# PRSC-2101-THCFM-1V3_eagle7.net
KiCad netlist of a schematic drawn in EAGLE
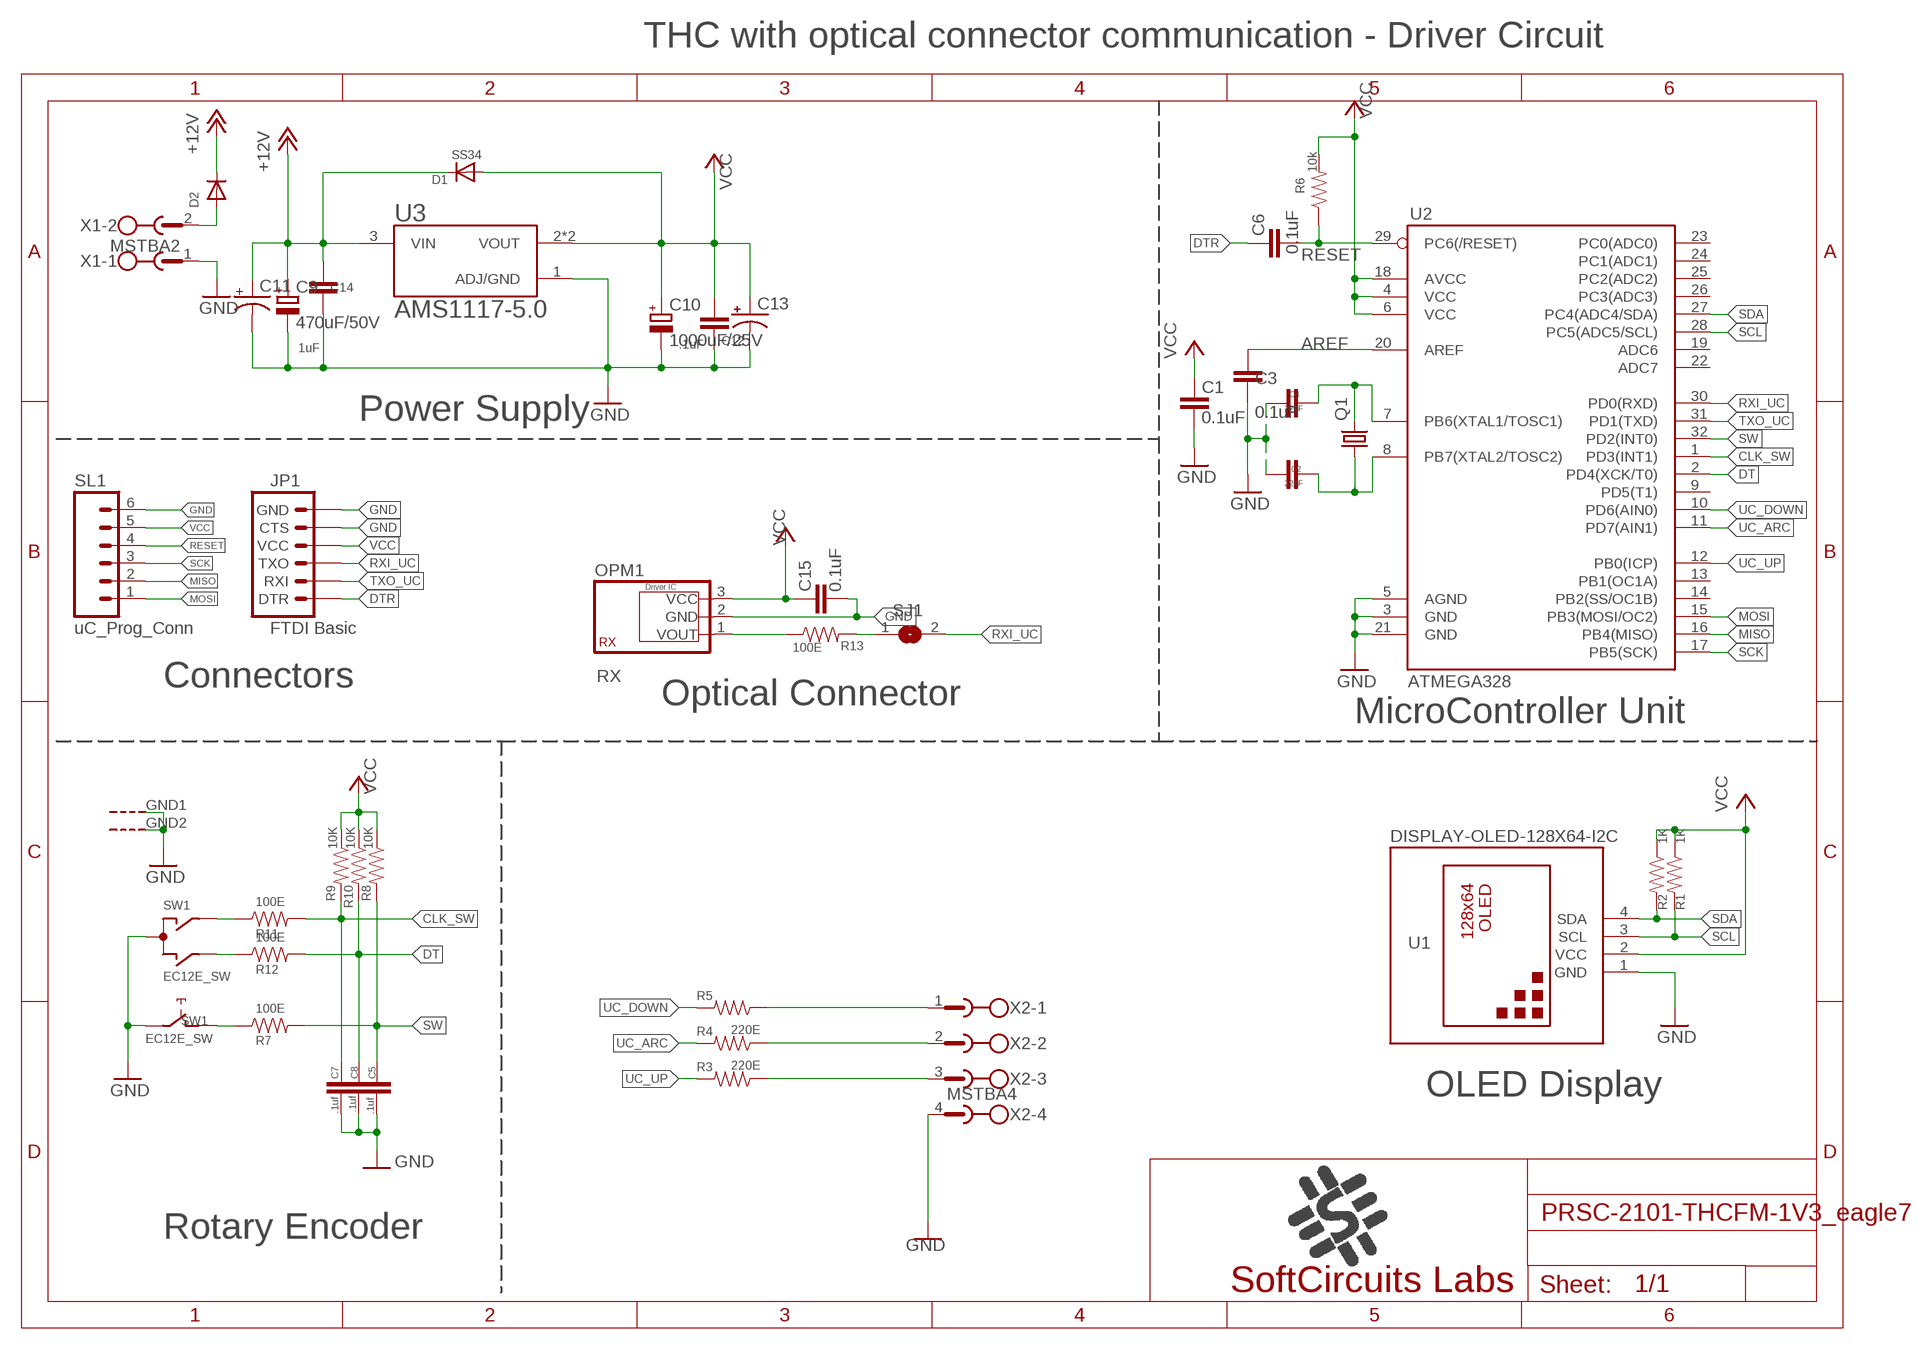
[diagram p0: schematic, sheet 1]

(export (version "E")
  (design (tool "Eeschema 10.0.6"))
  (components
    (comp (ref "C1")
      (value "0.1uF")
      (footprint "eagle-import:C1206")
      (libsource (lib "eagle-import") (part "C-EUC1206"))
    )
    (comp (ref "C2")
      (value "22pF")
      (footprint "eagle-import:C1206")
      (libsource (lib "eagle-import") (part "C-EUC1206"))
    )
    (comp (ref "C3")
      (value "0.1uF")
      (footprint "eagle-import:C1206")
      (libsource (lib "eagle-import") (part "C-EUC1206"))
    )
    (comp (ref "C4")
      (value "22pF")
      (footprint "eagle-import:C1206")
      (libsource (lib "eagle-import") (part "C-EUC1206"))
    )
    (comp (ref "C5")
      (value ".1uf")
      (footprint "eagle-import:C1206")
      (libsource (lib "eagle-import") (part "C-EUC1206"))
    )
    (comp (ref "C6")
      (value "0.1uF")
      (footprint "eagle-import:C1206")
      (libsource (lib "eagle-import") (part "C-EUC1206"))
    )
    (comp (ref "C7")
      (value ".1uf")
      (footprint "eagle-import:C1206")
      (libsource (lib "eagle-import") (part "C-EUC1206"))
    )
    (comp (ref "C8")
      (value ".1uf")
      (footprint "eagle-import:C1206")
      (libsource (lib "eagle-import") (part "C-EUC1206"))
    )
    (comp (ref "C9")
      (value "470uF/50V")
      (footprint "eagle-import:153CLV-1010")
      (libsource (lib "eagle-import") (part "CPOL-EU153CLV-1010"))
    )
    (comp (ref "C10")
      (value "1000uF/25V")
      (footprint "eagle-import:153CLV-1010")
      (libsource (lib "eagle-import") (part "CPOL-EU153CLV-1010"))
    )
    (comp (ref "C11")
      (value "CAP_POL3528-KIT")
      (footprint "eagle-import:EIA3528-KIT")
      (libsource (lib "eagle-import") (part "CAP_POL3528-KIT"))
    )
    (comp (ref "C12")
      (value ".1uF")
      (footprint "eagle-import:1206")
      (libsource (lib "eagle-import") (part "CAP1206"))
    )
    (comp (ref "C13")
      (value "CAP_POL3528-KIT")
      (footprint "eagle-import:EIA3528-KIT")
      (libsource (lib "eagle-import") (part "CAP_POL3528-KIT"))
    )
    (comp (ref "C14")
      (value "1uF")
      (footprint "eagle-import:1206")
      (libsource (lib "eagle-import") (part "CAP1206"))
    )
    (comp (ref "C15")
      (value "0.1uF")
      (footprint "eagle-import:C1206")
      (libsource (lib "eagle-import") (part "C-EUC1206"))
    )
    (comp (ref "D1")
      (value "SS34")
      (footprint "eagle-import:SMADIODE")
      (libsource (lib "eagle-import") (part "DIODESMA"))
    )
    (comp (ref "D2")
      (value "DIODESMA")
      (footprint "eagle-import:SMADIODE")
      (libsource (lib "eagle-import") (part "DIODESMA"))
    )
    (comp (ref "JP1")
      (value "FTDI Basic")
      (footprint "eagle-import:1X06")
      (libsource (lib "eagle-import") (part "ARDUINO_SERIAL_PROGRAMPTH"))
    )
    (comp (ref "LOGO100")
      (value "SC_LOGO")
      (footprint "eagle-import:SC_LOGO")
      (libsource (lib "eagle-import") (part "SC_LOGO"))
    )
    (comp (ref "OPM1")
      (value "RX")
      (footprint "eagle-import:TOSLINK_DQ-025")
      (libsource (lib "eagle-import") (part "TOSLINK_DQR-025"))
    )
    (comp (ref "Q1")
      (value "CRYSTALHC49UP")
      (footprint "eagle-import:HC49UP")
      (libsource (lib "eagle-import") (part "CRYSTALHC49UP"))
    )
    (comp (ref "R1")
      (value "1K")
      (footprint "eagle-import:1206")
      (libsource (lib "eagle-import") (part "RESISTOR1206"))
    )
    (comp (ref "R2")
      (value "1K")
      (footprint "eagle-import:1206")
      (libsource (lib "eagle-import") (part "RESISTOR1206"))
    )
    (comp (ref "R3")
      (value "220E")
      (footprint "eagle-import:1206")
      (libsource (lib "eagle-import") (part "RESISTOR1206"))
    )
    (comp (ref "R4")
      (value "220E")
      (footprint "eagle-import:1206")
      (libsource (lib "eagle-import") (part "RESISTOR1206"))
    )
    (comp (ref "R5")
      (value "220E")
      (footprint "eagle-import:1206")
      (libsource (lib "eagle-import") (part "RESISTOR1206"))
    )
    (comp (ref "R6")
      (value "10k")
      (footprint "eagle-import:1206")
      (libsource (lib "eagle-import") (part "RESISTOR1206"))
    )
    (comp (ref "R7")
      (value "100E")
      (footprint "eagle-import:1206")
      (libsource (lib "eagle-import") (part "RESISTOR1206"))
    )
    (comp (ref "R8")
      (value "10K")
      (footprint "eagle-import:1206")
      (libsource (lib "eagle-import") (part "RESISTOR1206"))
    )
    (comp (ref "R9")
      (value "10K")
      (footprint "eagle-import:1206")
      (libsource (lib "eagle-import") (part "RESISTOR1206"))
    )
    (comp (ref "R10")
      (value "10K")
      (footprint "eagle-import:1206")
      (libsource (lib "eagle-import") (part "RESISTOR1206"))
    )
    (comp (ref "R11")
      (value "100E")
      (footprint "eagle-import:1206")
      (libsource (lib "eagle-import") (part "RESISTOR1206"))
    )
    (comp (ref "R12")
      (value "100E")
      (footprint "eagle-import:1206")
      (libsource (lib "eagle-import") (part "RESISTOR1206"))
    )
    (comp (ref "R13")
      (value "100E")
      (footprint "eagle-import:1206")
      (libsource (lib "eagle-import") (part "RESISTOR1206"))
    )
    (comp (ref "SJ1") (value "SJ") (footprint "eagle-import:SJ") (libsource (lib "eagle-import") (part "SJ")))
    (comp (ref "SL1")
      (value "uC_Prog_Conn")
      (footprint "eagle-import:06P")
      (libsource (lib "eagle-import") (part "M06"))
    )
    (comp (ref "SW1")
      (value "EC12E_SW")
      (footprint "eagle-import:ALPS_EC12E_SW")
      (fields (field (name "MPN") "EC12E2424407"))
      (libsource (lib "eagle-import") (part "EC12E_SW"))
    )
    (comp (ref "U1")
      (value "DISPLAY-OLED-128X64-I2C")
      (footprint "eagle-import:DISPLAY-OLED-128X64-I2C")
      (libsource (lib "eagle-import") (part "DISPLAY-OLED-128X64-I2C"))
    )
    (comp (ref "U2")
      (value "ATMEGA328")
      (footprint "eagle-import:TQFP32-08")
      (libsource (lib "eagle-import") (part "ATMEGA168"))
    )
    (comp (ref "U3")
      (value "AMS1117-5.0")
      (footprint "eagle-import:SOT229P700X180-4N")
      (fields (field (name "MF") "Advanced Monolithic Systems"))
      (libsource (lib "eagle-import") (part "AMS1117-5.0"))
    )
    (comp (ref "X1")
      (value "MSTBA2")
      (footprint "eagle-import:MSTBA2")
      (fields (field (name "MF") "FARNELL") (field (name "MPN") "1757242"))
      (libsource (lib "eagle-import") (part "MSTBA2"))
    )
    (comp (ref "X2")
      (value "MSTBA4")
      (footprint "eagle-import:MSTBA4")
      (fields (field (name "MF") "FARNELL") (field (name "MPN") "1757268"))
      (libsource (lib "eagle-import") (part "MSTBA4"))
    )
  )
  (nets
    (net (code "1") (name "+12V") (class "Default")
      (node (ref "C11") (pin "A") (pinfunction "+_A") (pintype "passive"))
      (node (ref "C14") (pin "1") (pinfunction "1_1") (pintype "passive"))
      (node (ref "C9") (pin "+") (pinfunction "+_+") (pintype "passive"))
      (node (ref "D1") (pin "C") (pinfunction "C_C") (pintype "passive"))
      (node (ref "D2") (pin "C") (pinfunction "C_C") (pintype "passive"))
      (node (ref "U3") (pin "3") (pinfunction "VIN_3") (pintype "input"))
    )
    (net (code "2") (name "/AREF") (class "Default")
      (node (ref "C3") (pin "2") (pinfunction "2_2") (pintype "passive"))
      (node (ref "U2") (pin "20") (pinfunction "AREF_20") (pintype "bidirectional"))
    )
    (net (code "3") (name "CLK_SW") (class "Default")
      (node (ref "C7") (pin "1") (pinfunction "1_1") (pintype "passive"))
      (node (ref "R11") (pin "2") (pinfunction "2_2") (pintype "passive"))
      (node (ref "R9") (pin "2") (pinfunction "2_2") (pintype "passive"))
      (node (ref "U2") (pin "1") (pinfunction "PD3(INT1)_1") (pintype "bidirectional"))
    )
    (net (code "4") (name "DT") (class "Default")
      (node (ref "C8") (pin "1") (pinfunction "1_1") (pintype "passive"))
      (node (ref "R10") (pin "2") (pinfunction "2_2") (pintype "passive"))
      (node (ref "R12") (pin "2") (pinfunction "2_2") (pintype "passive"))
      (node (ref "U2") (pin "2") (pinfunction "PD4(XCK/T0)_2") (pintype "bidirectional"))
    )
    (net (code "5") (name "DTR") (class "Default")
      (node (ref "C6") (pin "2") (pinfunction "2_2") (pintype "passive"))
      (node (ref "JP1") (pin "1") (pinfunction "DTR_1") (pintype "passive"))
    )
    (net (code "6") (name "GND") (class "Default")
      (node (ref "C1") (pin "1") (pinfunction "1_1") (pintype "passive"))
      (node (ref "C10") (pin "-") (pinfunction "-_-") (pintype "passive"))
      (node (ref "C11") (pin "C") (pinfunction "-_C") (pintype "passive"))
      (node (ref "C12") (pin "2") (pinfunction "2_2") (pintype "passive"))
      (node (ref "C13") (pin "C") (pinfunction "-_C") (pintype "passive"))
      (node (ref "C14") (pin "2") (pinfunction "2_2") (pintype "passive"))
      (node (ref "C15") (pin "1") (pinfunction "1_1") (pintype "passive"))
      (node (ref "C2") (pin "2") (pinfunction "2_2") (pintype "passive"))
      (node (ref "C3") (pin "1") (pinfunction "1_1") (pintype "passive"))
      (node (ref "C4") (pin "2") (pinfunction "2_2") (pintype "passive"))
      (node (ref "C5") (pin "2") (pinfunction "2_2") (pintype "passive"))
      (node (ref "C7") (pin "2") (pinfunction "2_2") (pintype "passive"))
      (node (ref "C8") (pin "2") (pinfunction "2_2") (pintype "passive"))
      (node (ref "C9") (pin "-") (pinfunction "-_-") (pintype "passive"))
      (node (ref "JP1") (pin "5") (pinfunction "CTS_5") (pintype "passive"))
      (node (ref "JP1") (pin "6") (pinfunction "GND_6") (pintype "passive"))
      (node (ref "OPM1") (pin "2") (pinfunction "GND_2") (pintype "passive"))
      (node (ref "SL1") (pin "6") (pinfunction "6_6") (pintype "passive"))
      (node (ref "SW1") (pin "C") (pinfunction "C_C") (pintype "passive"))
      (node (ref "SW1") (pin "E") (pinfunction "2_E") (pintype "passive"))
      (node (ref "SW1") (pin "GND1") (pinfunction "G_GND1") (pintype "passive"))
      (node (ref "SW1") (pin "GND2") (pinfunction "G_GND2") (pintype "passive"))
      (node (ref "U1") (pin "1") (pinfunction "GND_1") (pintype "power_in"))
      (node (ref "U2") (pin "21") (pinfunction "GND_21") (pintype "bidirectional"))
      (node (ref "U2") (pin "3") (pinfunction "GND_3") (pintype "bidirectional"))
      (node (ref "U2") (pin "5") (pinfunction "AGND_5") (pintype "bidirectional"))
      (node (ref "U3") (pin "1") (pinfunction "ADJ/GND_1") (pintype "power_in"))
      (node (ref "X1") (pin "1") (pinfunction "1_1") (pintype "passive"))
      (node (ref "X2") (pin "4") (pinfunction "1_4") (pintype "passive"))
    )
    (net (code "7") (name "MISO") (class "Default")
      (node (ref "SL1") (pin "2") (pinfunction "2_2") (pintype "passive"))
      (node (ref "U2") (pin "16") (pinfunction "PB4(MISO)_16") (pintype "bidirectional"))
    )
    (net (code "8") (name "MOSI") (class "Default")
      (node (ref "SL1") (pin "1") (pinfunction "1_1") (pintype "passive"))
      (node (ref "U2") (pin "15") (pinfunction "PB3(MOSI/OC2)_15") (pintype "bidirectional"))
    )
    (net (code "9") (name "Net-(OPM1-VOUT)") (class "Default")
      (node (ref "OPM1") (pin "1") (pinfunction "VOUT_1") (pintype "passive"))
      (node (ref "R13") (pin "1") (pinfunction "1_1") (pintype "passive"))
    )
    (net (code "10") (name "Net-(R5-Pad1)") (class "Default")
      (node (ref "R5") (pin "1") (pinfunction "1_1") (pintype "passive"))
      (node (ref "X2") (pin "1") (pinfunction "1_1") (pintype "passive"))
    )
    (net (code "11") (name "Net-(R11-Pad1)") (class "Default")
      (node (ref "R11") (pin "1") (pinfunction "1_1") (pintype "passive"))
      (node (ref "SW1") (pin "A") (pinfunction "A_A") (pintype "passive"))
    )
    (net (code "12") (name "Net-(R12-Pad1)") (class "Default")
      (node (ref "R12") (pin "1") (pinfunction "1_1") (pintype "passive"))
      (node (ref "SW1") (pin "B") (pinfunction "B_B") (pintype "passive"))
    )
    (net (code "13") (name "Net-(R13-Pad2)") (class "Default")
      (node (ref "R13") (pin "2") (pinfunction "2_2") (pintype "passive"))
      (node (ref "SJ1") (pin "1") (pinfunction "1_1") (pintype "passive"))
    )
    (net (code "14") (name "Net-(SW1B-1)") (class "Default")
      (node (ref "R7") (pin "1") (pinfunction "1_1") (pintype "passive"))
      (node (ref "SW1") (pin "D") (pinfunction "1_D") (pintype "passive"))
    )
    (net (code "15") (name "Net-(U2-PB6(XTAL1{slash}TOSC1))") (class "Default")
      (node (ref "C4") (pin "1") (pinfunction "1_1") (pintype "passive"))
      (node (ref "Q1") (pin "2") (pinfunction "2_2") (pintype "passive"))
      (node (ref "U2") (pin "7") (pinfunction "PB6(XTAL1/TOSC1)_7") (pintype "bidirectional"))
    )
    (net (code "16") (name "Net-(U2-PB7(XTAL2{slash}TOSC2))") (class "Default")
      (node (ref "C2") (pin "1") (pinfunction "1_1") (pintype "passive"))
      (node (ref "Q1") (pin "1") (pinfunction "1_1") (pintype "passive"))
      (node (ref "U2") (pin "8") (pinfunction "PB7(XTAL2/TOSC2)_8") (pintype "bidirectional"))
    )
    (net (code "17") (name "Net-(X1B-1)") (class "Default")
      (node (ref "D2") (pin "A") (pinfunction "A_A") (pintype "passive"))
      (node (ref "X1") (pin "2") (pinfunction "1_2") (pintype "passive"))
    )
    (net (code "18") (name "Net-(X2B-1)") (class "Default")
      (node (ref "R4") (pin "1") (pinfunction "1_1") (pintype "passive"))
      (node (ref "X2") (pin "2") (pinfunction "1_2") (pintype "passive"))
    )
    (net (code "19") (name "Net-(X2C-1)") (class "Default")
      (node (ref "R3") (pin "1") (pinfunction "1_1") (pintype "passive"))
      (node (ref "X2") (pin "3") (pinfunction "1_3") (pintype "passive"))
    )
    (net (code "20") (name "RESET") (class "Default")
      (node (ref "C6") (pin "1") (pinfunction "1_1") (pintype "passive"))
      (node (ref "R6") (pin "1") (pinfunction "1_1") (pintype "passive"))
      (node (ref "SL1") (pin "4") (pinfunction "4_4") (pintype "passive"))
      (node (ref "U2") (pin "29") (pinfunction "PC6(/RESET)_29") (pintype "bidirectional"))
    )
    (net (code "21") (name "RXI_UC") (class "Default")
      (node (ref "JP1") (pin "3") (pinfunction "TXO_3") (pintype "passive"))
      (node (ref "SJ1") (pin "2") (pinfunction "2_2") (pintype "passive"))
      (node (ref "U2") (pin "30") (pinfunction "PD0(RXD)_30") (pintype "bidirectional"))
    )
    (net (code "22") (name "SCK") (class "Default")
      (node (ref "SL1") (pin "3") (pinfunction "3_3") (pintype "passive"))
      (node (ref "U2") (pin "17") (pinfunction "PB5(SCK)_17") (pintype "bidirectional"))
    )
    (net (code "23") (name "SCL") (class "Default")
      (node (ref "R1") (pin "2") (pinfunction "2_2") (pintype "passive"))
      (node (ref "U1") (pin "3") (pinfunction "SCL_3") (pintype "bidirectional"))
      (node (ref "U2") (pin "28") (pinfunction "PC5(ADC5/SCL)_28") (pintype "bidirectional"))
    )
    (net (code "24") (name "SDA") (class "Default")
      (node (ref "R2") (pin "2") (pinfunction "2_2") (pintype "passive"))
      (node (ref "U1") (pin "4") (pinfunction "SDA_4") (pintype "bidirectional"))
      (node (ref "U2") (pin "27") (pinfunction "PC4(ADC4/SDA)_27") (pintype "bidirectional"))
    )
    (net (code "25") (name "SW") (class "Default")
      (node (ref "C5") (pin "1") (pinfunction "1_1") (pintype "passive"))
      (node (ref "R7") (pin "2") (pinfunction "2_2") (pintype "passive"))
      (node (ref "R8") (pin "2") (pinfunction "2_2") (pintype "passive"))
      (node (ref "U2") (pin "32") (pinfunction "PD2(INT0)_32") (pintype "bidirectional"))
    )
    (net (code "26") (name "TXO_UC") (class "Default")
      (node (ref "JP1") (pin "2") (pinfunction "RXI_2") (pintype "passive"))
      (node (ref "U2") (pin "31") (pinfunction "PD1(TXD)_31") (pintype "bidirectional"))
    )
    (net (code "27") (name "UC_ARC") (class "Default")
      (node (ref "R4") (pin "2") (pinfunction "2_2") (pintype "passive"))
      (node (ref "U2") (pin "11") (pinfunction "PD7(AIN1)_11") (pintype "bidirectional"))
    )
    (net (code "28") (name "UC_DOWN") (class "Default")
      (node (ref "R5") (pin "2") (pinfunction "2_2") (pintype "passive"))
      (node (ref "U2") (pin "10") (pinfunction "PD6(AIN0)_10") (pintype "bidirectional"))
    )
    (net (code "29") (name "UC_UP") (class "Default")
      (node (ref "R3") (pin "2") (pinfunction "2_2") (pintype "passive"))
      (node (ref "U2") (pin "12") (pinfunction "PB0(ICP)_12") (pintype "bidirectional"))
    )
    (net (code "30") (name "VCC") (class "Default")
      (node (ref "C1") (pin "2") (pinfunction "2_2") (pintype "passive"))
      (node (ref "C10") (pin "+") (pinfunction "+_+") (pintype "passive"))
      (node (ref "C12") (pin "1") (pinfunction "1_1") (pintype "passive"))
      (node (ref "C13") (pin "A") (pinfunction "+_A") (pintype "passive"))
      (node (ref "C15") (pin "2") (pinfunction "2_2") (pintype "passive"))
      (node (ref "D1") (pin "A") (pinfunction "A_A") (pintype "passive"))
      (node (ref "JP1") (pin "4") (pinfunction "VCC_4") (pintype "passive"))
      (node (ref "OPM1") (pin "3") (pinfunction "VCC_3") (pintype "bidirectional"))
      (node (ref "R1") (pin "1") (pinfunction "1_1") (pintype "passive"))
      (node (ref "R10") (pin "1") (pinfunction "1_1") (pintype "passive"))
      (node (ref "R2") (pin "1") (pinfunction "1_1") (pintype "passive"))
      (node (ref "R6") (pin "2") (pinfunction "2_2") (pintype "passive"))
      (node (ref "R8") (pin "1") (pinfunction "1_1") (pintype "passive"))
      (node (ref "R9") (pin "1") (pinfunction "1_1") (pintype "passive"))
      (node (ref "SL1") (pin "5") (pinfunction "5_5") (pintype "passive"))
      (node (ref "U1") (pin "2") (pinfunction "VCC_2") (pintype "power_in"))
      (node (ref "U2") (pin "18") (pinfunction "AVCC_18") (pintype "bidirectional"))
      (node (ref "U2") (pin "4") (pinfunction "VCC_4") (pintype "bidirectional"))
      (node (ref "U2") (pin "6") (pinfunction "VCC_6") (pintype "bidirectional"))
      (node (ref "U3") (pin "2") (pinfunction "VOUT_2") (pintype "output"))
      (node (ref "U3") (pin "4") (pinfunction "VOUT_4") (pintype "output"))
    )
    (net (code "31") (name "unconnected-(U2-ADC6-Pad19)") (class "Default")
      (node (ref "U2") (pin "19") (pinfunction "ADC6_19") (pintype "bidirectional"))
    )
    (net (code "32") (name "unconnected-(U2-ADC7-Pad22)") (class "Default")
      (node (ref "U2") (pin "22") (pinfunction "ADC7_22") (pintype "bidirectional"))
    )
    (net (code "33") (name "unconnected-(U2-PB1(OC1A)-Pad13)") (class "Default")
      (node (ref "U2") (pin "13") (pinfunction "PB1(OC1A)_13") (pintype "bidirectional"))
    )
    (net (code "34") (name "unconnected-(U2-PB2(SS{slash}OC1B)-Pad14)") (class "Default")
      (node (ref "U2") (pin "14") (pinfunction "PB2(SS/OC1B)_14") (pintype "bidirectional"))
    )
    (net (code "35") (name "unconnected-(U2-PC0(ADC0)-Pad23)") (class "Default")
      (node (ref "U2") (pin "23") (pinfunction "PC0(ADC0)_23") (pintype "bidirectional"))
    )
    (net (code "36") (name "unconnected-(U2-PC1(ADC1)-Pad24)") (class "Default")
      (node (ref "U2") (pin "24") (pinfunction "PC1(ADC1)_24") (pintype "bidirectional"))
    )
    (net (code "37") (name "unconnected-(U2-PC2(ADC2)-Pad25)") (class "Default")
      (node (ref "U2") (pin "25") (pinfunction "PC2(ADC2)_25") (pintype "bidirectional"))
    )
    (net (code "38") (name "unconnected-(U2-PC3(ADC3)-Pad26)") (class "Default")
      (node (ref "U2") (pin "26") (pinfunction "PC3(ADC3)_26") (pintype "bidirectional"))
    )
    (net (code "39") (name "unconnected-(U2-PD5(T1)-Pad9)") (class "Default")
      (node (ref "U2") (pin "9") (pinfunction "PD5(T1)_9") (pintype "bidirectional"))
    )
  )
)
